# 01_Power.net
KiCad netlist of a schematic drawn in Altium Designer
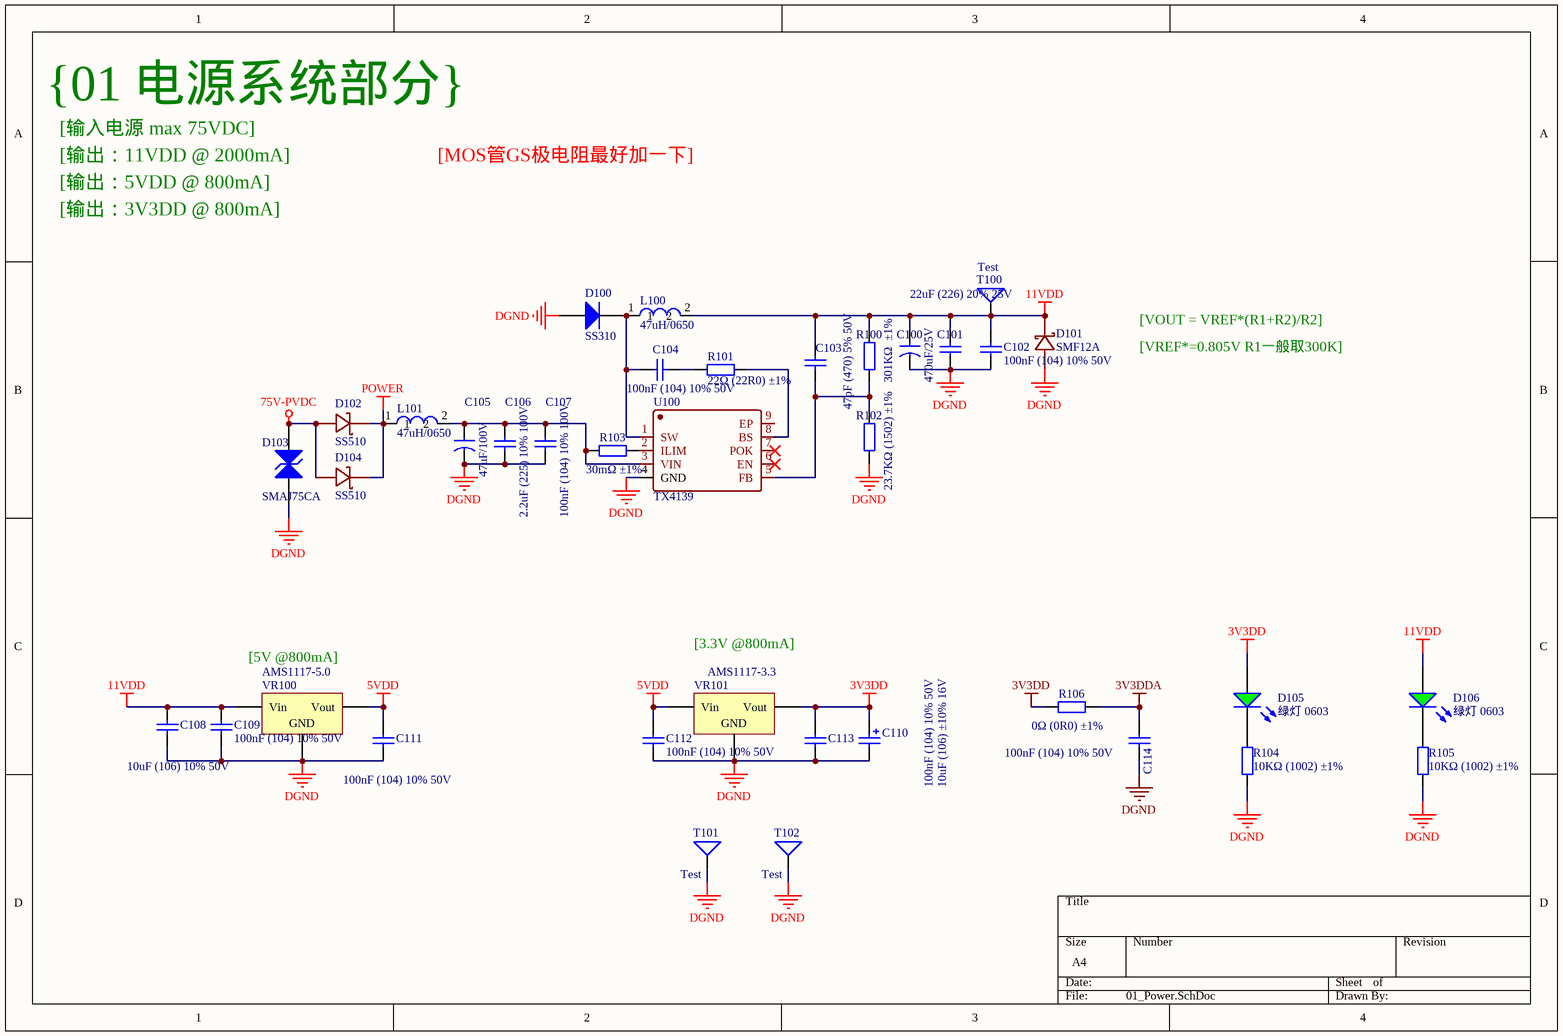
[diagram p0: 01_Power.SchDoc]

(export (version "E")
  (design (tool "Eeschema 10.0.6"))
  (components
    (comp (ref "C100")
      (value "470uF/25V")
      (footprint "47UF/100V")
      (libsource (lib "RayPCB20210502") (part "CapSMT220u_16V"))
    )
    (comp (ref "C101")
      (value "22uF (226) 20% 25V")
      (footprint "LC-0805_C")
      (description "贴片电容")
      (libsource (lib "Miscellaneous Devices LC") (part "0805 22uF (226) 20% 25V"))
    )
    (comp (ref "C102")
      (value "100nF (104) 10% 50V")
      (footprint "LC-0603_C")
      (description "贴片电容")
      (libsource (lib "Miscellaneous Devices LC") (part "0603 100nF (104) 10% 50V"))
    )
    (comp (ref "C103")
      (value "47pF (470) 5% 50V")
      (footprint "LC-0603_C")
      (description "贴片电容")
      (libsource (lib "Miscellaneous Devices LC") (part "0603 47pF (470) 5% 50V"))
    )
    (comp (ref "C104")
      (value "100nF (104) 10% 50V")
      (footprint "LC-0603_C")
      (description "贴片电容")
      (libsource (lib "Miscellaneous Devices LC") (part "0603 100nF (104) 10% 50V"))
    )
    (comp (ref "C105")
      (value "47uF/100V")
      (footprint "47UF/100V")
      (libsource (lib "RayPCB20210502") (part "CapSMT220u_16V"))
    )
    (comp (ref "C106")
      (value "2.2uF (225) 10% 100V")
      (footprint "LC-1206_C")
      (description "贴片电容")
      (libsource (lib "Miscellaneous Devices LC") (part "1206 2.2uF (225) 10% 50V"))
    )
    (comp (ref "C107")
      (value "100nF (104) 10% 100V")
      (footprint "LC-1206_C")
      (description "贴片电容")
      (libsource (lib "Miscellaneous Devices LC") (part "1206 100nF (104) 10% 50V"))
    )
    (comp (ref "C108")
      (value "10uF (106) 10% 50V")
      (footprint "LC-1206_C")
      (description "贴片电容")
      (libsource (lib "Miscellaneous Devices LC") (part "1206 10uF (106) 10% 50V"))
    )
    (comp (ref "C109")
      (value "100nF (104) 10% 50V")
      (footprint "LC-0603_C")
      (description "贴片电容")
      (libsource (lib "Miscellaneous Devices LC") (part "0603 100nF (104) 10% 50V"))
    )
    (comp (ref "C110")
      (value "10uF (106) ±10% 16V")
      (footprint "LC-CASE-A_3216")
      (description "钽电容")
      (libsource (lib "Miscellaneous Devices LC") (part "3216 10uF (106) 10% 16V"))
    )
    (comp (ref "C111")
      (value "100nF (104) 10% 50V")
      (footprint "LC-0603_C")
      (description "贴片电容")
      (libsource (lib "Miscellaneous Devices LC") (part "0603 100nF (104) 10% 50V"))
    )
    (comp (ref "C112")
      (value "100nF (104) 10% 50V")
      (footprint "LC-0603_C")
      (description "贴片电容")
      (libsource (lib "Miscellaneous Devices LC") (part "0603 100nF (104) 10% 50V"))
    )
    (comp (ref "C113")
      (value "100nF (104) 10% 50V")
      (footprint "LC-0603_C")
      (description "贴片电容")
      (libsource (lib "Miscellaneous Devices LC") (part "0603 100nF (104) 10% 50V"))
    )
    (comp (ref "C114")
      (value "100nF (104) 10% 50V")
      (footprint "LC-0603_C")
      (description "贴片电容")
      (libsource (lib "Miscellaneous Devices LC") (part "0603 100nF (104) 10% 50V"))
    )
    (comp (ref "D100")
      (value "SS310")
      (footprint "LC-SMA(DO-214AC)_S1")
      (description "二极管")
      (libsource (lib "Miscellaneous Devices LC") (part "SMA(DO-214AC) SS54"))
    )
    (comp (ref "D101")
      (value "SMF12A")
      (footprint "SMF12A - duplicate")
      (libsource (lib "RayPCB20210502") (part "SMF12A"))
    )
    (comp (ref "D102") (value "SS510") (footprint "SS510") (libsource (lib "RayPCB20210502") (part "SS510")))
    (comp (ref "D103")
      (value "SMAJ75CA")
      (footprint "LC-SMB(DO-214AA)_S1")
      (description "TVS")
      (libsource (lib "Miscellaneous Devices LC") (part "SMB/DO-214AA P6SMB6.8CA"))
    )
    (comp (ref "D104") (value "SS510") (footprint "SS510") (libsource (lib "RayPCB20210502") (part "SS510")))
    (comp (ref "D105")
      (value "绿灯 0603")
      (footprint "LC-0603_LED_S1")
      (description "发光二极管")
      (libsource (lib "Miscellaneous Devices LC") (part "0603 绿灯"))
    )
    (comp (ref "D106")
      (value "绿灯 0603")
      (footprint "LC-0603_LED_S1")
      (description "发光二极管")
      (libsource (lib "Miscellaneous Devices LC") (part "0603 绿灯"))
    )
    (comp (ref "L100")
      (value "47uH/0650")
      (footprint "0650_47uH")
      (libsource (lib "RayPCB20210502") (part "Inductor"))
    )
    (comp (ref "L101")
      (value "47uH/0650")
      (footprint "0650_47uH")
      (libsource (lib "RayPCB20210502") (part "Inductor"))
    )
    (comp (ref "R100")
      (value "301KΩ  ±1%")
      (footprint "LC-0603_R")
      (description "贴片电阻")
      (libsource (lib "Miscellaneous Devices LC") (part "0603 330KΩ (3303) 1%"))
    )
    (comp (ref "R101")
      (value "22Ω (22R0) ±1%")
      (footprint "LC-0603_R")
      (description "贴片电阻")
      (libsource (lib "Miscellaneous Devices LC") (part "0603 22Ω (22R0) 1%"))
    )
    (comp (ref "R102")
      (value "23.7KΩ (1502) ±1%")
      (footprint "LC-0603_R")
      (description "贴片电阻")
      (libsource (lib "Miscellaneous Devices LC") (part "0603 15KΩ (1502) 1%"))
    )
    (comp (ref "R103")
      (value "30mΩ ±1%")
      (footprint "LC-0603_R")
      (description "贴片电阻")
      (libsource (lib "Miscellaneous Devices LC") (part "0603 100KΩ (1003) 1%"))
    )
    (comp (ref "R104")
      (value "10KΩ (1002) ±1%")
      (footprint "LC-0603_R")
      (description "贴片电阻")
      (libsource (lib "Miscellaneous Devices LC") (part "0603 10KΩ (1002) 1%"))
    )
    (comp (ref "R105")
      (value "10KΩ (1002) ±1%")
      (footprint "LC-0603_R")
      (description "贴片电阻")
      (libsource (lib "Miscellaneous Devices LC") (part "0603 10KΩ (1002) 1%"))
    )
    (comp (ref "R106")
      (value "0Ω (0R0) ±1%")
      (footprint "LC-0603_R")
      (description "贴片电阻")
      (libsource (lib "Miscellaneous Devices LC") (part "0603 0Ω (0R0) 1%"))
    )
    (comp (ref "T100")
      (value "Test")
      (footprint "Testpoint")
      (libsource (lib "RayPCB20210502") (part "TestPad"))
    )
    (comp (ref "T101")
      (value "Test")
      (footprint "Testpoint")
      (libsource (lib "RayPCB20210502") (part "TestPad"))
    )
    (comp (ref "T102")
      (value "Test")
      (footprint "Testpoint")
      (libsource (lib "RayPCB20210502") (part "TestPad"))
    )
    (comp (ref "U100")
      (value "TX4139")
      (footprint "ESOP8")
      (libsource (lib "RayPCB20210502") (part "TX4139"))
    )
    (comp (ref "VR100")
      (value "AMS1117-5.0")
      (footprint "LC-SOT-223")
      (description "低压差线性稳压(LDO)")
      (libsource (lib "Miscellaneous Devices LC") (part "SOT-223 AMS1117-5.0"))
    )
    (comp (ref "VR101")
      (value "AMS1117-3.3")
      (footprint "LC-SOT-223")
      (description "低压差线性稳压(LDO)")
      (libsource (lib "Miscellaneous Devices LC") (part "SOT-223 AMS1117-3.3"))
    )
  )
  (nets
    (net (code "1") (name "3V3DD") (class "Default")
      (node (ref "C110") (pin "1") (pinfunction "1_1") (pintype "passive"))
      (node (ref "C113") (pin "2") (pinfunction "2_2") (pintype "passive"))
      (node (ref "D105") (pin "A") (pinfunction "A_A") (pintype "passive"))
      (node (ref "R106") (pin "1") (pinfunction "1_1") (pintype "passive"))
      (node (ref "VR101") (pin "2") (pinfunction "Vout_2") (pintype "passive"))
    )
    (net (code "2") (name "3V3DDA") (class "Default")
      (node (ref "C114") (pin "2") (pinfunction "2_2") (pintype "passive"))
      (node (ref "R106") (pin "2") (pinfunction "2_2") (pintype "passive"))
    )
    (net (code "3") (name "5VDD") (class "Default")
      (node (ref "C111") (pin "2") (pinfunction "2_2") (pintype "passive"))
      (node (ref "C112") (pin "2") (pinfunction "2_2") (pintype "passive"))
      (node (ref "VR100") (pin "2") (pinfunction "Vout_2") (pintype "passive"))
      (node (ref "VR101") (pin "3") (pinfunction "Vin_3") (pintype "passive"))
    )
    (net (code "4") (name "11VDD") (class "Default")
      (node (ref "C100") (pin "1") (pintype "passive"))
      (node (ref "C101") (pin "2") (pinfunction "2_2") (pintype "passive"))
      (node (ref "C102") (pin "2") (pinfunction "2_2") (pintype "passive"))
      (node (ref "C103") (pin "2") (pinfunction "2_2") (pintype "passive"))
      (node (ref "C108") (pin "2") (pinfunction "2_2") (pintype "passive"))
      (node (ref "C109") (pin "2") (pinfunction "2_2") (pintype "passive"))
      (node (ref "D101") (pin "1") (pinfunction "K_1") (pintype "passive"))
      (node (ref "D106") (pin "A") (pinfunction "A_A") (pintype "passive"))
      (node (ref "L100") (pin "2") (pinfunction "2_2") (pintype "passive"))
      (node (ref "R100") (pin "2") (pinfunction "2_2") (pintype "passive"))
      (node (ref "T100") (pin "1") (pinfunction "1_1") (pintype "passive"))
      (node (ref "VR100") (pin "3") (pinfunction "Vin_3") (pintype "passive"))
    )
    (net (code "5") (name "75V-PVDC") (class "Default")
      (node (ref "D102") (pin "2") (pinfunction "2_2") (pintype "passive"))
      (node (ref "D103") (pin "2") (pinfunction "K_2") (pintype "passive"))
      (node (ref "D104") (pin "2") (pinfunction "2_2") (pintype "passive"))
    )
    (net (code "6") (name "DGND") (class "Default")
      (node (ref "C100") (pin "2") (pintype "passive"))
      (node (ref "C101") (pin "1") (pinfunction "1_1") (pintype "passive"))
      (node (ref "C102") (pin "1") (pinfunction "1_1") (pintype "passive"))
      (node (ref "C105") (pin "2") (pintype "passive"))
      (node (ref "C106") (pin "1") (pinfunction "1_1") (pintype "passive"))
      (node (ref "C107") (pin "1") (pinfunction "1_1") (pintype "passive"))
      (node (ref "C108") (pin "1") (pinfunction "1_1") (pintype "passive"))
      (node (ref "C109") (pin "1") (pinfunction "1_1") (pintype "passive"))
      (node (ref "C110") (pin "2") (pinfunction "2_2") (pintype "passive"))
      (node (ref "C111") (pin "1") (pinfunction "1_1") (pintype "passive"))
      (node (ref "C112") (pin "1") (pinfunction "1_1") (pintype "passive"))
      (node (ref "C113") (pin "1") (pinfunction "1_1") (pintype "passive"))
      (node (ref "C114") (pin "1") (pinfunction "1_1") (pintype "passive"))
      (node (ref "D100") (pin "1") (pinfunction "A_1") (pintype "passive"))
      (node (ref "D101") (pin "2") (pinfunction "A_2") (pintype "passive"))
      (node (ref "D103") (pin "1") (pinfunction "A_1") (pintype "passive"))
      (node (ref "R102") (pin "1") (pinfunction "1_1") (pintype "passive"))
      (node (ref "R104") (pin "1") (pinfunction "1_1") (pintype "passive"))
      (node (ref "R105") (pin "1") (pinfunction "1_1") (pintype "passive"))
      (node (ref "T101") (pin "1") (pinfunction "1_1") (pintype "passive"))
      (node (ref "T102") (pin "1") (pinfunction "1_1") (pintype "passive"))
      (node (ref "U100") (pin "4") (pinfunction "GND_4") (pintype "passive"))
      (node (ref "VR100") (pin "1") (pinfunction "GND_1") (pintype "passive"))
      (node (ref "VR101") (pin "1") (pinfunction "GND_1") (pintype "passive"))
    )
    (net (code "7") (name "Net-(C104-Pad2)") (class "Default")
      (node (ref "C104") (pin "2") (pinfunction "2_2") (pintype "passive"))
      (node (ref "R101") (pin "1") (pinfunction "1_1") (pintype "passive"))
    )
    (net (code "8") (name "Net-(D100-K)") (class "Default")
      (node (ref "C104") (pin "1") (pinfunction "1_1") (pintype "passive"))
      (node (ref "D100") (pin "2") (pinfunction "K_2") (pintype "passive"))
      (node (ref "L100") (pin "1") (pinfunction "1_1") (pintype "passive"))
      (node (ref "U100") (pin "1") (pinfunction "SW_1") (pintype "passive"))
    )
    (net (code "9") (name "Net-(D105-PadK)") (class "Default")
      (node (ref "D105") (pin "K") (pinfunction "K_K") (pintype "passive"))
      (node (ref "R104") (pin "2") (pinfunction "2_2") (pintype "passive"))
    )
    (net (code "10") (name "Net-(D106-PadK)") (class "Default")
      (node (ref "D106") (pin "K") (pinfunction "K_K") (pintype "passive"))
      (node (ref "R105") (pin "2") (pinfunction "2_2") (pintype "passive"))
    )
    (net (code "11") (name "Net-(U100-BS)") (class "Default")
      (node (ref "R101") (pin "2") (pinfunction "2_2") (pintype "passive"))
      (node (ref "U100") (pin "8") (pinfunction "BS_8") (pintype "passive"))
    )
    (net (code "12") (name "Net-(U100-FB)") (class "Default")
      (node (ref "C103") (pin "1") (pinfunction "1_1") (pintype "passive"))
      (node (ref "R100") (pin "1") (pinfunction "1_1") (pintype "passive"))
      (node (ref "R102") (pin "2") (pinfunction "2_2") (pintype "passive"))
      (node (ref "U100") (pin "5") (pinfunction "FB_5") (pintype "passive"))
    )
    (net (code "13") (name "Net-(U100-ILIM)") (class "Default")
      (node (ref "R103") (pin "1") (pinfunction "1_1") (pintype "passive"))
      (node (ref "U100") (pin "2") (pinfunction "ILIM_2") (pintype "passive"))
    )
    (net (code "14") (name "Net-(U100-VIN)") (class "Default")
      (node (ref "C105") (pin "1") (pintype "passive"))
      (node (ref "C106") (pin "2") (pinfunction "2_2") (pintype "passive"))
      (node (ref "C107") (pin "2") (pinfunction "2_2") (pintype "passive"))
      (node (ref "L101") (pin "2") (pinfunction "2_2") (pintype "passive"))
      (node (ref "R103") (pin "2") (pinfunction "2_2") (pintype "passive"))
      (node (ref "U100") (pin "3") (pinfunction "VIN_3") (pintype "passive"))
    )
    (net (code "15") (name "POWER") (class "Default")
      (node (ref "D102") (pin "1") (pinfunction "1_1") (pintype "passive"))
      (node (ref "D104") (pin "1") (pinfunction "1_1") (pintype "passive"))
      (node (ref "L101") (pin "1") (pinfunction "1_1") (pintype "passive"))
    )
    (net (code "16") (name "unconnected-(U100-EN-Pad6)") (class "Default")
      (node (ref "U100") (pin "6") (pinfunction "EN_6") (pintype "passive+no_connect"))
    )
    (net (code "17") (name "unconnected-(U100-EP-Pad9)") (class "Default")
      (node (ref "U100") (pin "9") (pinfunction "EP_9") (pintype "passive"))
    )
    (net (code "18") (name "unconnected-(U100-POK-Pad7)") (class "Default")
      (node (ref "U100") (pin "7") (pinfunction "POK_7") (pintype "passive+no_connect"))
    )
  )
)
